# Controller.net
KiCad netlist of a schematic drawn in EAGLE
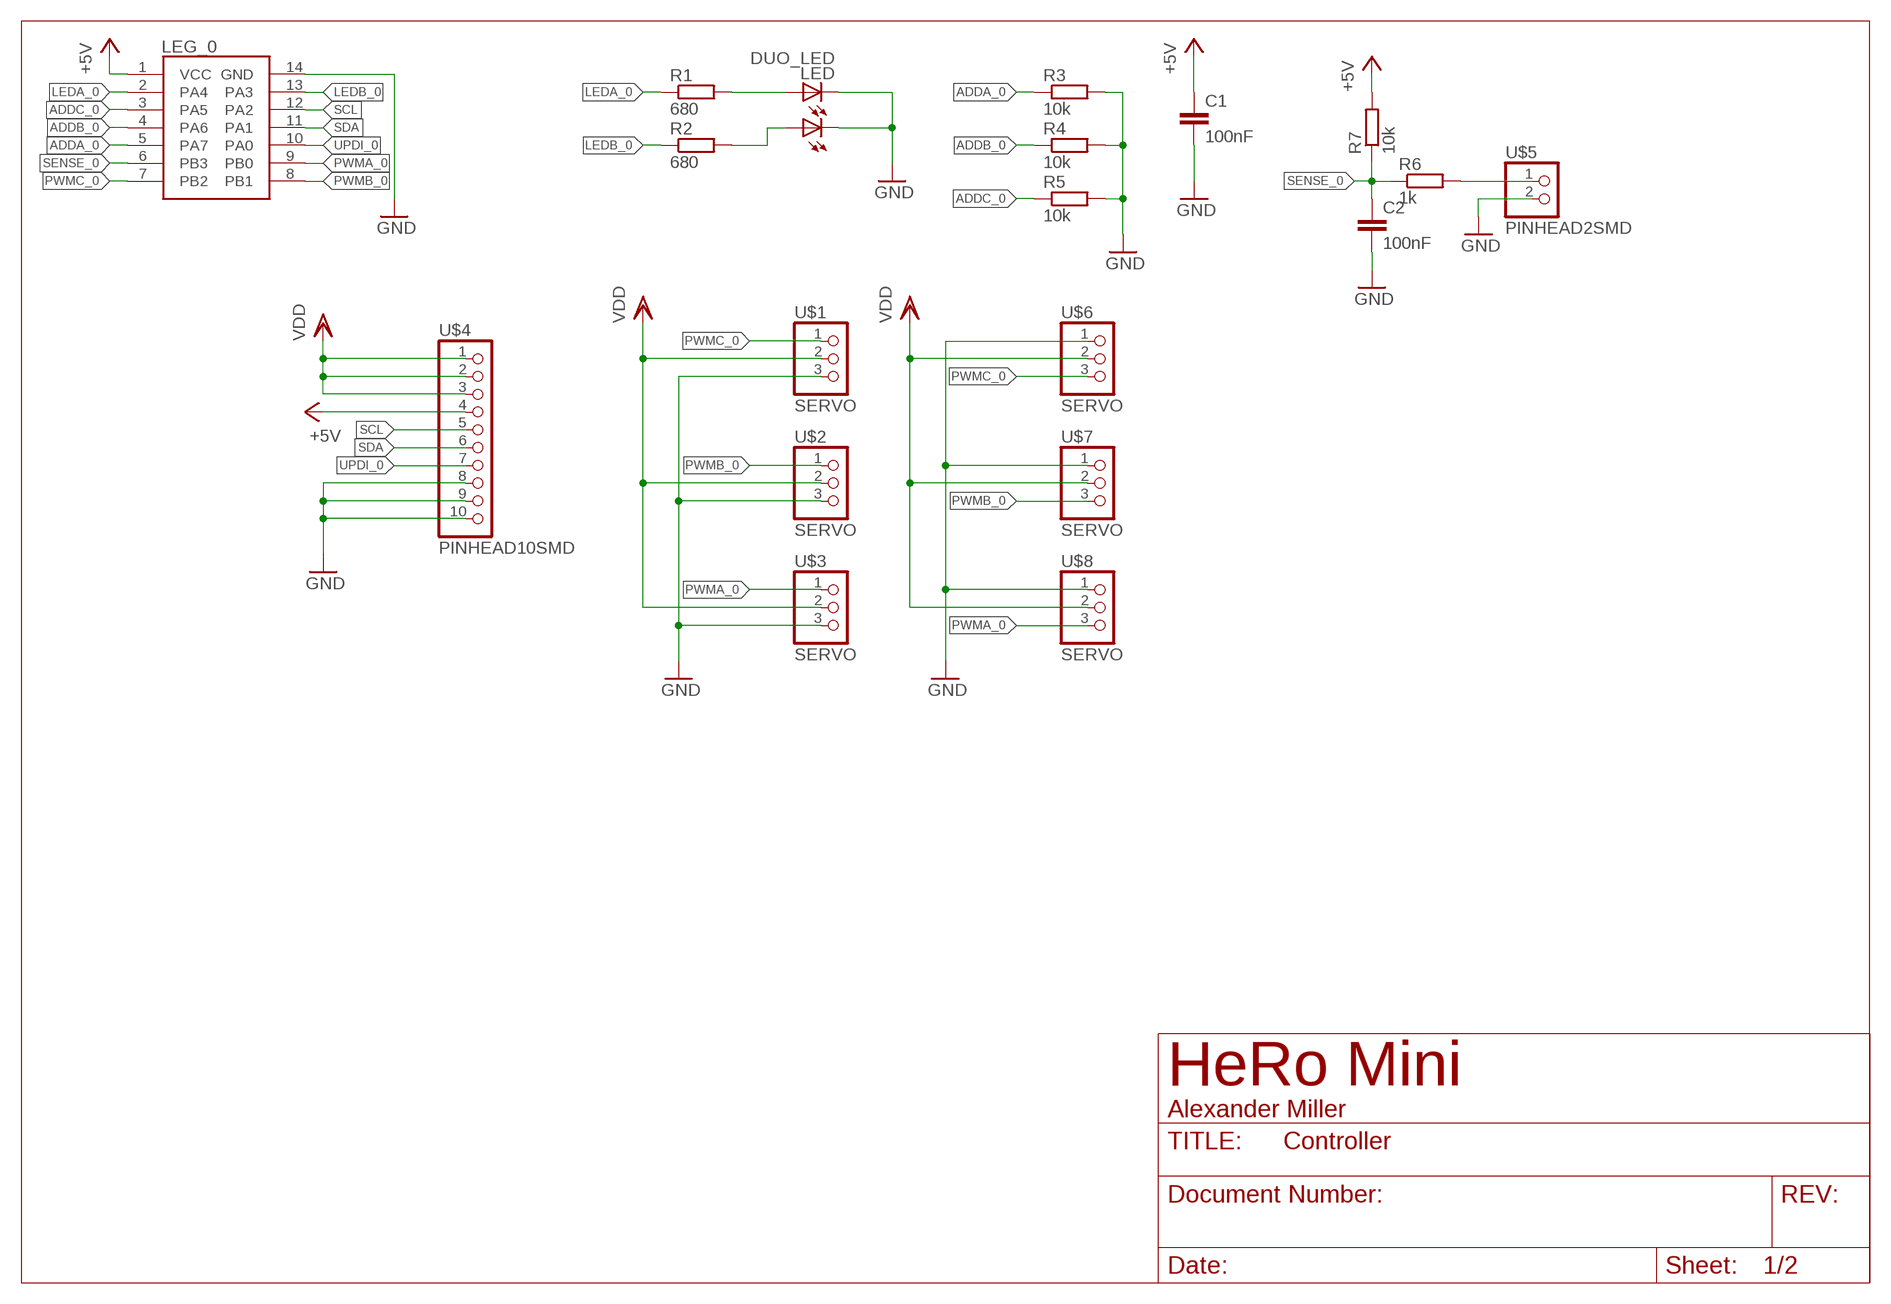
[diagram p0: schematic, sheet 1]
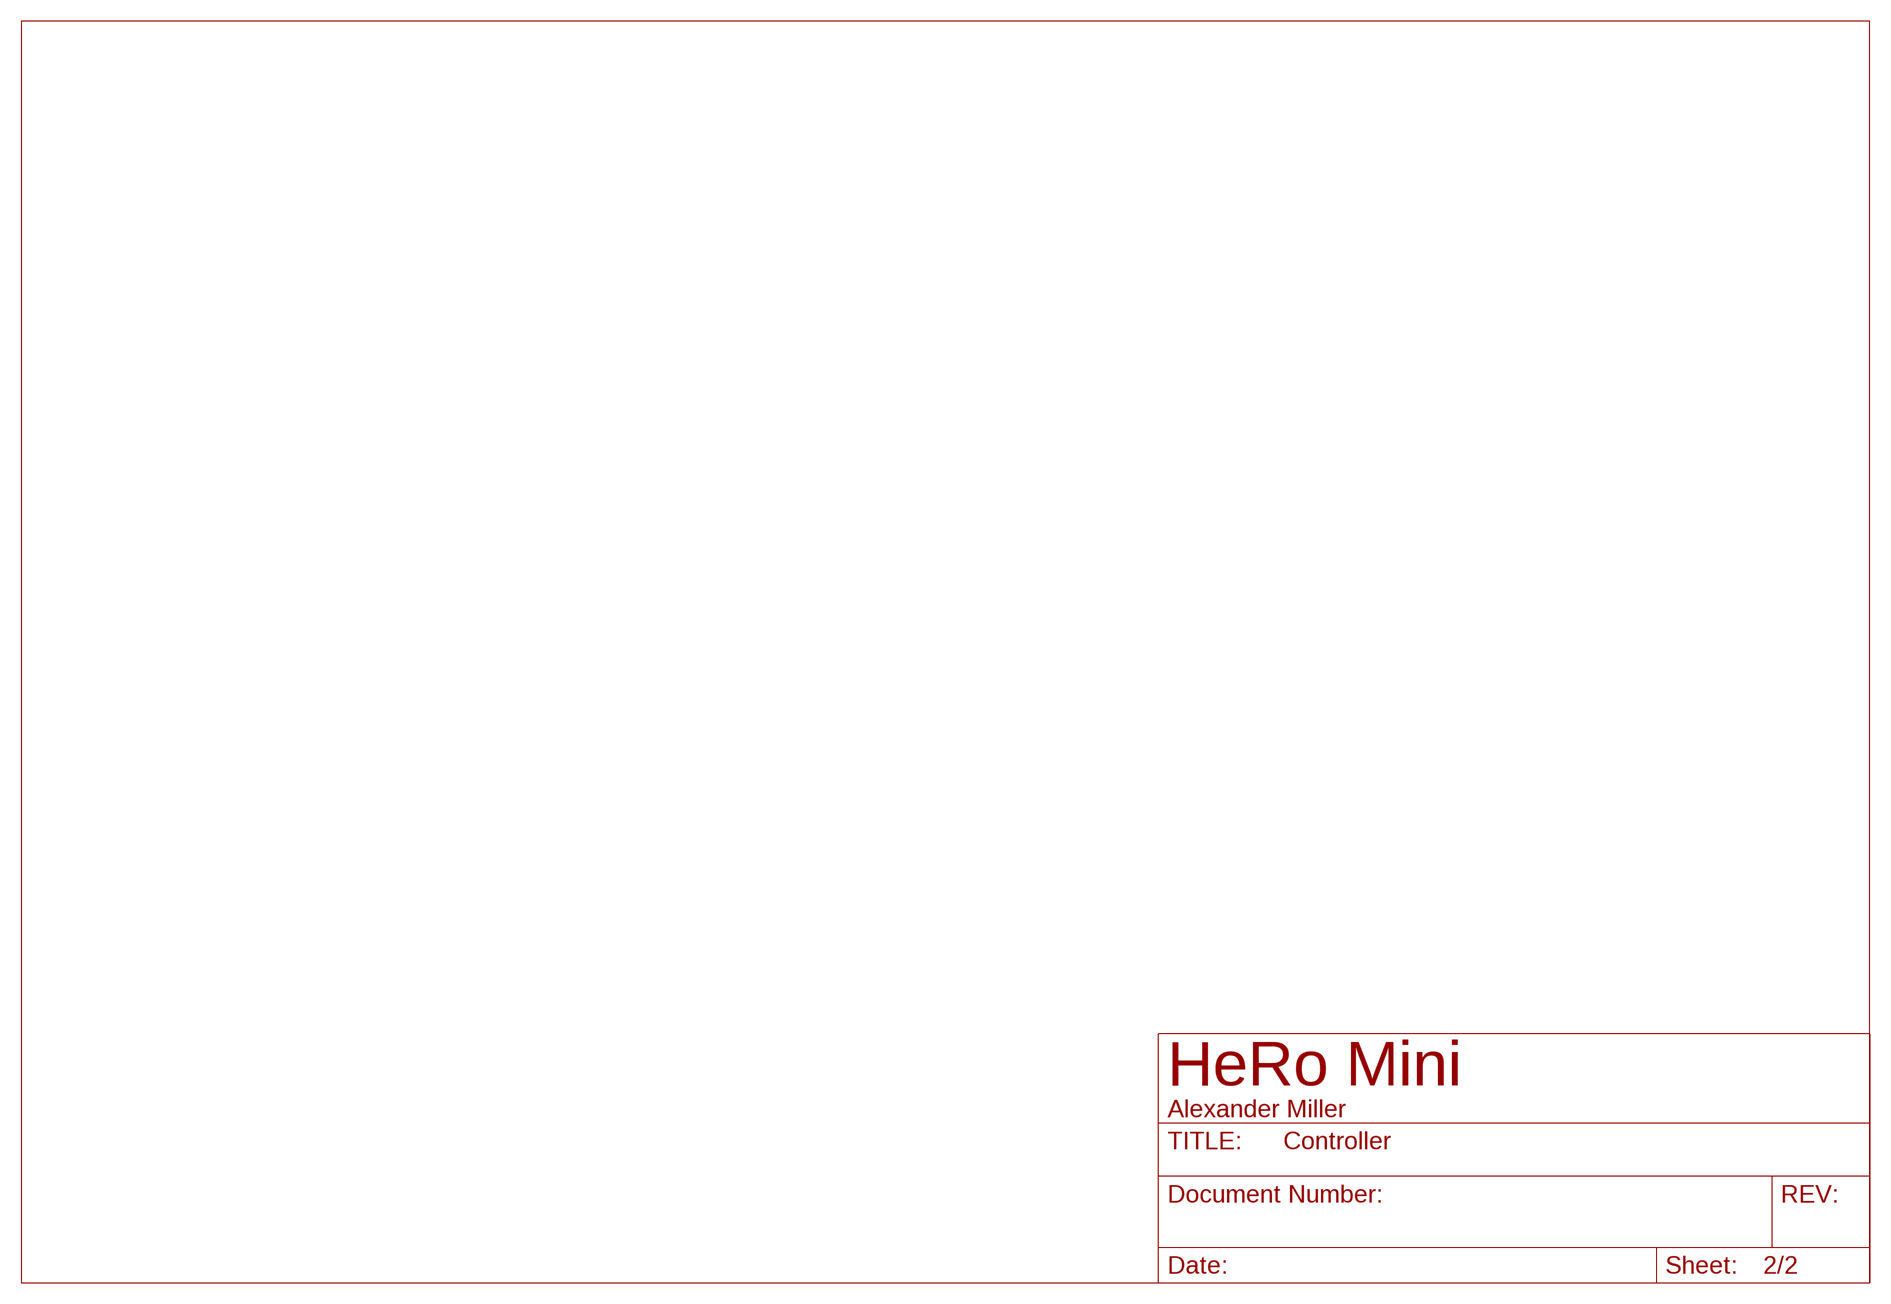
[diagram p1: schematic, sheet 2]

(export (version "E")
  (design (tool "Eeschema 10.0.6"))
  (components
    (comp (ref "C1")
      (value "100nF")
      (footprint "eagle-import:C0805")
      (libsource (lib "eagle-import") (part "C-EUC0805"))
    )
    (comp (ref "C2")
      (value "100nF")
      (footprint "eagle-import:C0805")
      (libsource (lib "eagle-import") (part "C-EUC0805"))
    )
    (comp (ref "LED")
      (value "DUO_LED")
      (footprint "eagle-import:DUO_LED")
      (libsource (lib "eagle-import") (part "DUO_LED"))
    )
    (comp (ref "LEG_0")
      (value "ATTINY16142")
      (footprint "eagle-import:SOIC127P600X175-14")
      (fields (field (name "SPICEPREFIX") "X"))
      (libsource (lib "eagle-import") (part "ATTINY16142"))
    )
    (comp (ref "R1")
      (value "680")
      (footprint "eagle-import:R0805")
      (libsource (lib "eagle-import") (part "R-EU_R0805"))
    )
    (comp (ref "R2")
      (value "680")
      (footprint "eagle-import:R0805")
      (libsource (lib "eagle-import") (part "R-EU_R0805"))
    )
    (comp (ref "R3")
      (value "10k")
      (footprint "eagle-import:R0805")
      (libsource (lib "eagle-import") (part "R-EU_R0805"))
    )
    (comp (ref "R4")
      (value "10k")
      (footprint "eagle-import:R0805")
      (libsource (lib "eagle-import") (part "R-EU_R0805"))
    )
    (comp (ref "R5")
      (value "10k")
      (footprint "eagle-import:R0805")
      (libsource (lib "eagle-import") (part "R-EU_R0805"))
    )
    (comp (ref "R6")
      (value "1k")
      (footprint "eagle-import:R0805")
      (libsource (lib "eagle-import") (part "R-EU_R0805"))
    )
    (comp (ref "R7")
      (value "10k")
      (footprint "eagle-import:R0805")
      (libsource (lib "eagle-import") (part "R-EU_R0805"))
    )
    (comp (ref "U$1")
      (value "SERVO")
      (footprint "eagle-import:SL12SMD058")
      (libsource (lib "eagle-import") (part "SERVO"))
    )
    (comp (ref "U$2")
      (value "SERVO")
      (footprint "eagle-import:SL12SMD058")
      (libsource (lib "eagle-import") (part "SERVO"))
    )
    (comp (ref "U$3")
      (value "SERVO")
      (footprint "eagle-import:SL12SMD058")
      (libsource (lib "eagle-import") (part "SERVO"))
    )
    (comp (ref "U$4")
      (value "PINHEAD10SMD")
      (footprint "eagle-import:PINHD10SMD")
      (libsource (lib "eagle-import") (part "PINHEAD10SMD"))
    )
    (comp (ref "U$5")
      (value "PINHEAD2SMD")
      (footprint "eagle-import:PINHD2SMD")
      (libsource (lib "eagle-import") (part "PINHEAD2SMD"))
    )
    (comp (ref "U$6")
      (value "SERVO")
      (footprint "eagle-import:SL12SMD058")
      (libsource (lib "eagle-import") (part "SERVO"))
    )
    (comp (ref "U$7")
      (value "SERVO")
      (footprint "eagle-import:SL12SMD058")
      (libsource (lib "eagle-import") (part "SERVO"))
    )
    (comp (ref "U$8")
      (value "SERVO")
      (footprint "eagle-import:SL12SMD058")
      (libsource (lib "eagle-import") (part "SERVO"))
    )
  )
  (nets
    (net (code "1") (name "+5V") (class "Default")
      (node (ref "C1") (pin "1") (pinfunction "1_1") (pintype "passive"))
      (node (ref "LEG_0") (pin "1") (pinfunction "VCC_1") (pintype "bidirectional"))
      (node (ref "R7") (pin "2") (pinfunction "2_2") (pintype "passive"))
      (node (ref "U$4") (pin "4") (pinfunction "4_4") (pintype "passive"))
    )
    (net (code "2") (name "ADDA_0") (class "Default")
      (node (ref "LEG_0") (pin "5") (pinfunction "PA7_5") (pintype "bidirectional"))
      (node (ref "R3") (pin "1") (pinfunction "1_1") (pintype "passive"))
    )
    (net (code "3") (name "ADDB_0") (class "Default")
      (node (ref "LEG_0") (pin "4") (pinfunction "PA6_4") (pintype "bidirectional"))
      (node (ref "R4") (pin "1") (pinfunction "1_1") (pintype "passive"))
    )
    (net (code "4") (name "ADDC_0") (class "Default")
      (node (ref "LEG_0") (pin "3") (pinfunction "PA5_3") (pintype "bidirectional"))
      (node (ref "R5") (pin "1") (pinfunction "1_1") (pintype "passive"))
    )
    (net (code "5") (name "GND") (class "Default")
      (node (ref "C1") (pin "2") (pinfunction "2_2") (pintype "passive"))
      (node (ref "C2") (pin "2") (pinfunction "2_2") (pintype "passive"))
      (node (ref "LED") (pin "CG") (pinfunction "CG_CG") (pintype "passive"))
      (node (ref "LED") (pin "CR") (pinfunction "CR_CR") (pintype "passive"))
      (node (ref "LEG_0") (pin "14") (pinfunction "GND_14") (pintype "bidirectional"))
      (node (ref "R3") (pin "2") (pinfunction "2_2") (pintype "passive"))
      (node (ref "R4") (pin "2") (pinfunction "2_2") (pintype "passive"))
      (node (ref "R5") (pin "2") (pinfunction "2_2") (pintype "passive"))
      (node (ref "U$1") (pin "3") (pinfunction "3_3") (pintype "passive"))
      (node (ref "U$2") (pin "3") (pinfunction "3_3") (pintype "passive"))
      (node (ref "U$3") (pin "3") (pinfunction "3_3") (pintype "passive"))
      (node (ref "U$4") (pin "10") (pinfunction "10_10") (pintype "passive"))
      (node (ref "U$4") (pin "8") (pinfunction "8_8") (pintype "passive"))
      (node (ref "U$4") (pin "9") (pinfunction "9_9") (pintype "passive"))
      (node (ref "U$5") (pin "2") (pinfunction "2_2") (pintype "passive"))
      (node (ref "U$6") (pin "1") (pinfunction "1_1") (pintype "passive"))
      (node (ref "U$7") (pin "1") (pinfunction "1_1") (pintype "passive"))
      (node (ref "U$8") (pin "1") (pinfunction "1_1") (pintype "passive"))
    )
    (net (code "6") (name "LEDA_0") (class "Default")
      (node (ref "LEG_0") (pin "2") (pinfunction "PA4_2") (pintype "bidirectional"))
      (node (ref "R1") (pin "1") (pinfunction "1_1") (pintype "passive"))
    )
    (net (code "7") (name "LEDB_0") (class "Default")
      (node (ref "LEG_0") (pin "13") (pinfunction "PA3_13") (pintype "bidirectional"))
      (node (ref "R2") (pin "1") (pinfunction "1_1") (pintype "passive"))
    )
    (net (code "8") (name "Net-(LED-PadAG)") (class "Default")
      (node (ref "LED") (pin "AG") (pinfunction "AG_AG") (pintype "passive"))
      (node (ref "R1") (pin "2") (pinfunction "2_2") (pintype "passive"))
    )
    (net (code "9") (name "Net-(LED-PadAR)") (class "Default")
      (node (ref "LED") (pin "AR") (pinfunction "AR_AR") (pintype "passive"))
      (node (ref "R2") (pin "2") (pinfunction "2_2") (pintype "passive"))
    )
    (net (code "10") (name "Net-(R6-Pad2)") (class "Default")
      (node (ref "R6") (pin "2") (pinfunction "2_2") (pintype "passive"))
      (node (ref "U$5") (pin "1") (pinfunction "1_1") (pintype "passive"))
    )
    (net (code "11") (name "PWMA_0") (class "Default")
      (node (ref "LEG_0") (pin "9") (pinfunction "PB0_9") (pintype "bidirectional"))
      (node (ref "U$3") (pin "1") (pinfunction "1_1") (pintype "passive"))
      (node (ref "U$8") (pin "3") (pinfunction "3_3") (pintype "passive"))
    )
    (net (code "12") (name "PWMB_0") (class "Default")
      (node (ref "LEG_0") (pin "8") (pinfunction "PB1_8") (pintype "bidirectional"))
      (node (ref "U$2") (pin "1") (pinfunction "1_1") (pintype "passive"))
      (node (ref "U$7") (pin "3") (pinfunction "3_3") (pintype "passive"))
    )
    (net (code "13") (name "PWMC_0") (class "Default")
      (node (ref "LEG_0") (pin "7") (pinfunction "PB2_7") (pintype "bidirectional"))
      (node (ref "U$1") (pin "1") (pinfunction "1_1") (pintype "passive"))
      (node (ref "U$6") (pin "3") (pinfunction "3_3") (pintype "passive"))
    )
    (net (code "14") (name "SCL") (class "Default")
      (node (ref "LEG_0") (pin "12") (pinfunction "PA2_12") (pintype "bidirectional"))
      (node (ref "U$4") (pin "5") (pinfunction "5_5") (pintype "passive"))
    )
    (net (code "15") (name "SDA") (class "Default")
      (node (ref "LEG_0") (pin "11") (pinfunction "PA1_11") (pintype "bidirectional"))
      (node (ref "U$4") (pin "6") (pinfunction "6_6") (pintype "passive"))
    )
    (net (code "16") (name "SENSE_0") (class "Default")
      (node (ref "C2") (pin "1") (pinfunction "1_1") (pintype "passive"))
      (node (ref "LEG_0") (pin "6") (pinfunction "PB3_6") (pintype "bidirectional"))
      (node (ref "R6") (pin "1") (pinfunction "1_1") (pintype "passive"))
      (node (ref "R7") (pin "1") (pinfunction "1_1") (pintype "passive"))
    )
    (net (code "17") (name "UPDI_0") (class "Default")
      (node (ref "LEG_0") (pin "10") (pinfunction "PA0_10") (pintype "bidirectional"))
      (node (ref "U$4") (pin "7") (pinfunction "7_7") (pintype "passive"))
    )
    (net (code "18") (name "VDD") (class "Default")
      (node (ref "U$1") (pin "2") (pinfunction "2_2") (pintype "passive"))
      (node (ref "U$2") (pin "2") (pinfunction "2_2") (pintype "passive"))
      (node (ref "U$3") (pin "2") (pinfunction "2_2") (pintype "passive"))
      (node (ref "U$4") (pin "1") (pinfunction "1_1") (pintype "passive"))
      (node (ref "U$4") (pin "2") (pinfunction "2_2") (pintype "passive"))
      (node (ref "U$4") (pin "3") (pinfunction "3_3") (pintype "passive"))
      (node (ref "U$6") (pin "2") (pinfunction "2_2") (pintype "passive"))
      (node (ref "U$7") (pin "2") (pinfunction "2_2") (pintype "passive"))
      (node (ref "U$8") (pin "2") (pinfunction "2_2") (pintype "passive"))
    )
  )
)
